# Sky_Sheet.net
KiCad netlist of a schematic drawn in Altium Designer
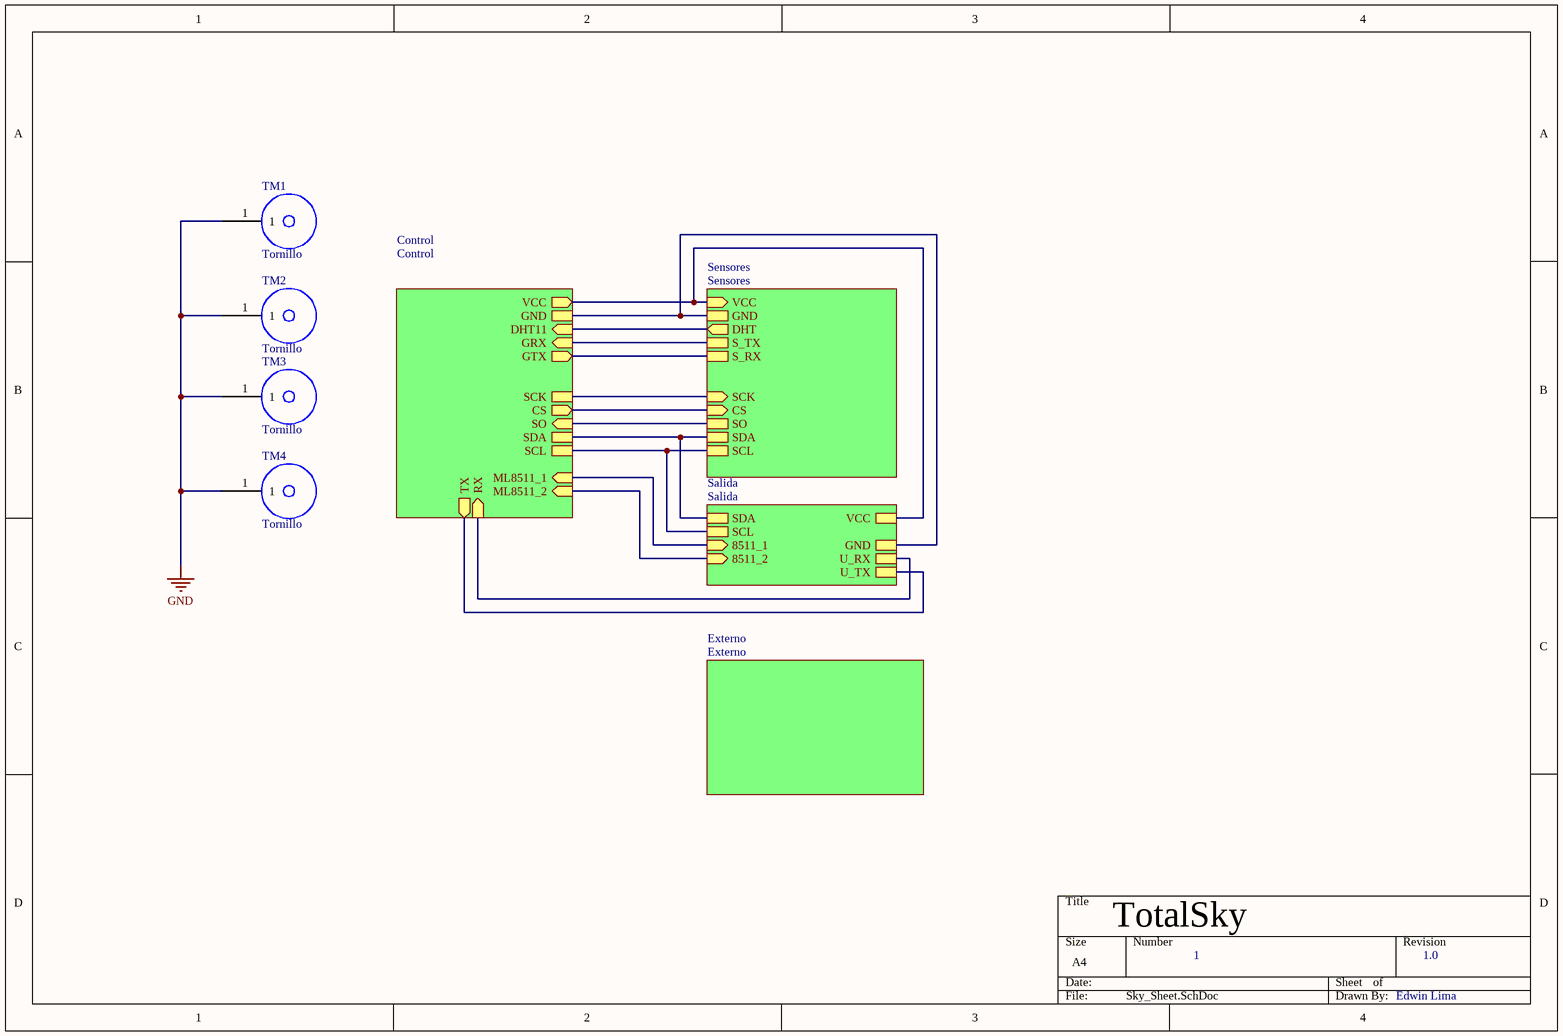
[diagram p0: Sky_Sheet.SchDoc]

(export (version "E")
  (design (tool "Eeschema 10.0.6"))
  (components
    (comp (ref "TM1")
      (value "Tornillo")
      (footprint "Tornillo M3")
      (libsource (lib "Sky_Schlib") (part "Tornillo"))
    )
    (comp (ref "TM2")
      (value "Tornillo")
      (footprint "Tornillo M3")
      (libsource (lib "Sky_Schlib") (part "Tornillo"))
    )
    (comp (ref "TM3")
      (value "Tornillo")
      (footprint "Tornillo M3")
      (libsource (lib "Sky_Schlib") (part "Tornillo"))
    )
    (comp (ref "TM4")
      (value "Tornillo")
      (footprint "Tornillo M3")
      (libsource (lib "Sky_Schlib") (part "Tornillo"))
    )
  )
  (nets
    (net (code "15") (name "GND") (class "Default")
      (node (ref "TM1") (pin "1") (pinfunction "1_1") (pintype "passive"))
      (node (ref "TM2") (pin "1") (pinfunction "1_1") (pintype "passive"))
      (node (ref "TM3") (pin "1") (pinfunction "1_1") (pintype "passive"))
      (node (ref "TM4") (pin "1") (pinfunction "1_1") (pintype "passive"))
    )
  )
)
